# Microcontroller.net
KiCad netlist of a schematic drawn in Altium Designer
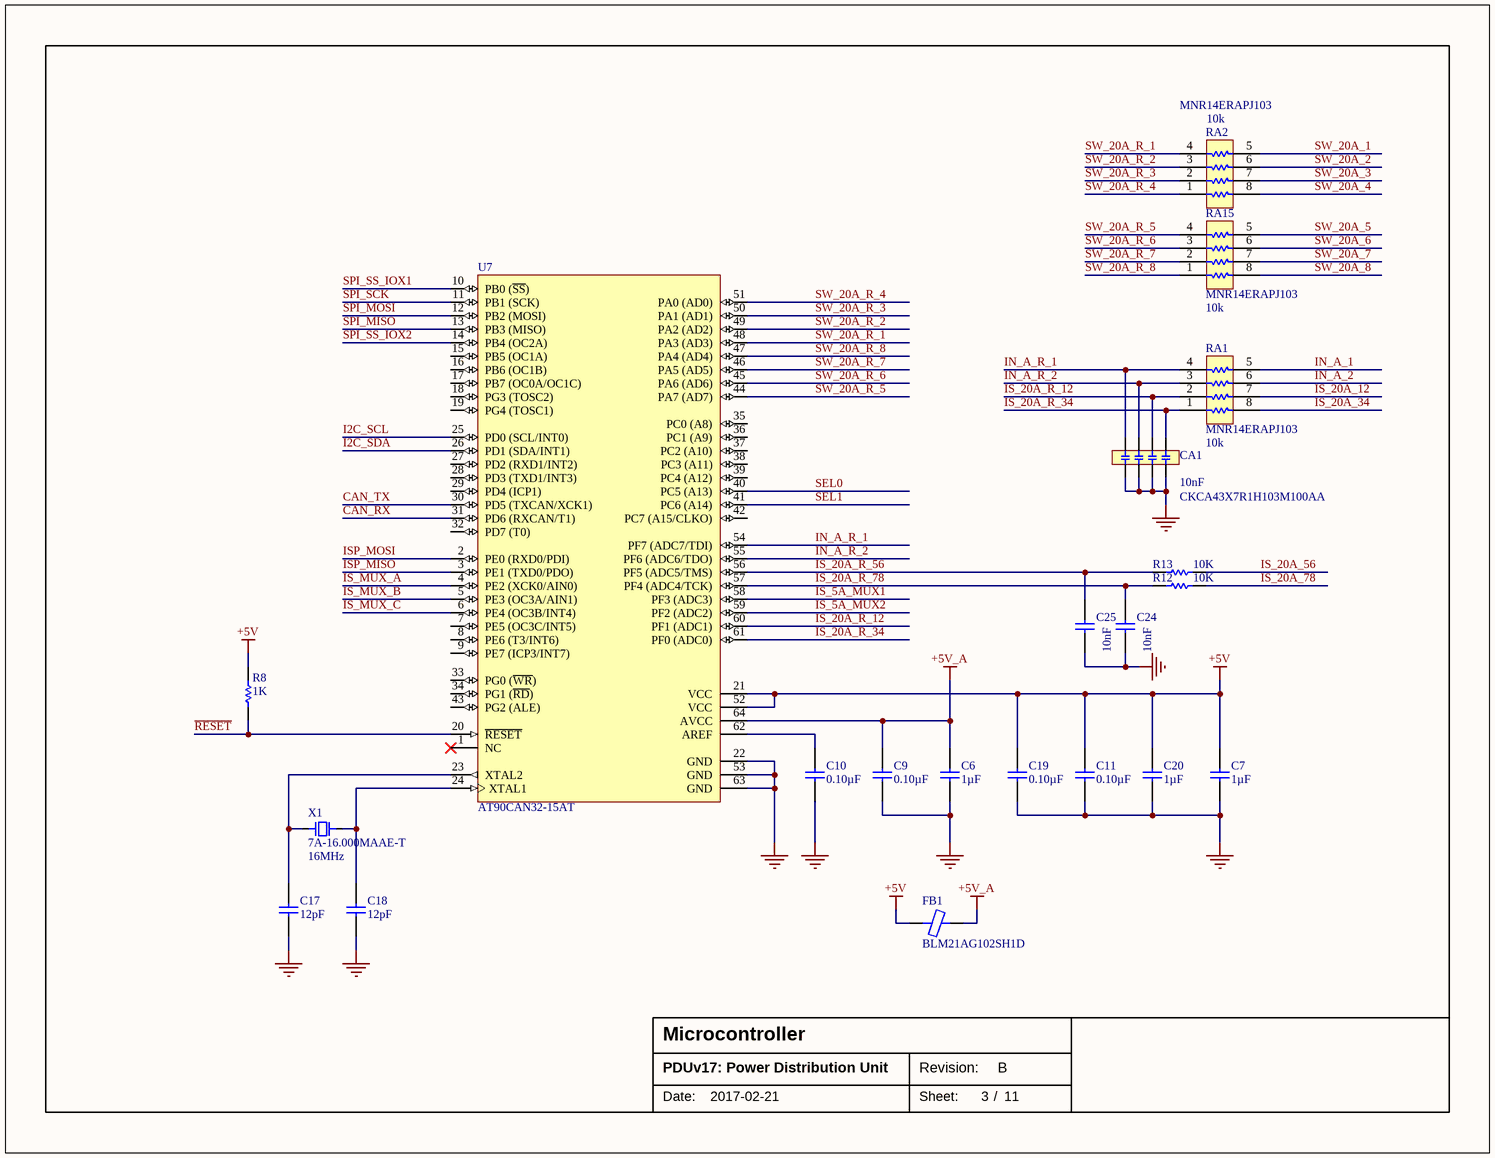
[diagram p0: Microcontroller.SchDoc]

(export (version "E")
  (design (tool "Eeschema 10.0.6"))
  (components
    (comp (ref "C6")
      (value "1µF")
      (footprint "CAP-0805-M")
      (fields
        (field (name "PART NUMBER") "CC0805KKX7R7BB105")
        (field (name "TOLERANCE") "±10%")
        (field (name "VOLTAGE") "16V")
      )
      (libsource (lib "Capacitors") (part "Capacitor"))
    )
    (comp (ref "C7")
      (value "1µF")
      (footprint "CAP-0805-M")
      (fields
        (field (name "PART NUMBER") "CC0805KKX7R7BB105")
        (field (name "TOLERANCE") "±10%")
        (field (name "VOLTAGE") "16V")
      )
      (libsource (lib "Capacitors") (part "Capacitor"))
    )
    (comp (ref "C9")
      (value "0.10µF")
      (footprint "CAP-0402-M")
      (fields
        (field (name "PART NUMBER") "CC0402KRX7R7BB104")
        (field (name "TOLERANCE") "±10%")
        (field (name "VOLTAGE") "16V")
      )
      (libsource (lib "Capacitors") (part "Capacitor"))
    )
    (comp (ref "C10")
      (value "0.10µF")
      (footprint "CAP-0402-M")
      (fields
        (field (name "PART NUMBER") "CC0402KRX7R7BB104")
        (field (name "TOLERANCE") "±10%")
        (field (name "VOLTAGE") "16V")
      )
      (libsource (lib "Capacitors") (part "Capacitor"))
    )
    (comp (ref "C11")
      (value "0.10µF")
      (footprint "CAP-0402-M")
      (fields
        (field (name "PART NUMBER") "CC0402KRX7R7BB104")
        (field (name "TOLERANCE") "±10%")
        (field (name "VOLTAGE") "16V")
      )
      (libsource (lib "Capacitors") (part "Capacitor"))
    )
    (comp (ref "C17")
      (value "12pF")
      (footprint "CAP-0402-M")
      (fields
        (field (name "PART NUMBER") "CC0402JRNPO9BN120")
        (field (name "TOLERANCE") "±5%")
        (field (name "VOLTAGE") "50V")
      )
      (libsource (lib "Capacitors") (part "Capacitor"))
    )
    (comp (ref "C18")
      (value "12pF")
      (footprint "CAP-0402-M")
      (fields
        (field (name "PART NUMBER") "CC0402JRNPO9BN120")
        (field (name "TOLERANCE") "±5%")
        (field (name "VOLTAGE") "50V")
      )
      (libsource (lib "Capacitors") (part "Capacitor"))
    )
    (comp (ref "C19")
      (value "0.10µF")
      (footprint "CAP-0402-M")
      (fields
        (field (name "PART NUMBER") "CC0402KRX7R7BB104")
        (field (name "TOLERANCE") "±10%")
        (field (name "VOLTAGE") "16V")
      )
      (libsource (lib "Capacitors") (part "Capacitor"))
    )
    (comp (ref "C20")
      (value "1µF")
      (footprint "CAP-0805-M")
      (fields
        (field (name "PART NUMBER") "CC0805KKX7R7BB105")
        (field (name "TOLERANCE") "±10%")
        (field (name "VOLTAGE") "16V")
      )
      (libsource (lib "Capacitors") (part "Capacitor"))
    )
    (comp (ref "C24")
      (value "10nF")
      (footprint "CAP-0402-M")
      (fields
        (field (name "PART NUMBER") "CC0402KRX7R7BB103")
        (field (name "TOLERANCE") "±10%")
        (field (name "VOLTAGE") "16V")
      )
      (libsource (lib "Capacitors") (part "Capacitor"))
    )
    (comp (ref "C25")
      (value "10nF")
      (footprint "CAP-0402-M")
      (fields
        (field (name "PART NUMBER") "CC0402KRX7R7BB103")
        (field (name "TOLERANCE") "±10%")
        (field (name "VOLTAGE") "16V")
      )
      (libsource (lib "Capacitors") (part "Capacitor"))
    )
    (comp (ref "CA1")
      (value "CKCA43X7R1H103M100AA")
      (footprint "CAF-80P319X159-8N")
      (fields (field (name "ALTIUM_VALUE") "10nF"))
      (libsource (lib "PDU-UV17") (part "CKCA43X7R1H103M100AA"))
    )
    (comp (ref "FB1")
      (value "BLM21AG102SH1D")
      (footprint "INDC2012X11N")
      (libsource (lib "PDU-UV17") (part "BLM21AG102SH1D"))
    )
    (comp (ref "R8")
      (value "1K")
      (footprint "RES-0603-M")
      (fields
        (field (name "PART NUMBER") "RC0603FR-071KL")
        (field (name "TOLERANCE") "1%")
        (field (name "POWER") "1/10 W")
      )
      (libsource (lib "Resistors") (part "Resistor"))
    )
    (comp (ref "R12")
      (value "10K")
      (footprint "RES-0603-M")
      (fields
        (field (name "PART NUMBER") "RC0603FR-0710KL")
        (field (name "TOLERANCE") "1%")
        (field (name "POWER") "1/10 W")
      )
      (libsource (lib "Resistors") (part "Resistor"))
    )
    (comp (ref "R13")
      (value "10K")
      (footprint "RES-0603-M")
      (fields
        (field (name "PART NUMBER") "RC0603FR-0710KL")
        (field (name "TOLERANCE") "1%")
        (field (name "POWER") "1/10 W")
      )
      (libsource (lib "Resistors") (part "Resistor"))
    )
    (comp (ref "RA1")
      (value "MNR14ERAPJ103")
      (footprint "CAC-80P319X150-8N")
      (fields (field (name "ALTIUM_VALUE") "10k"))
      (libsource (lib "PDU-UV17") (part "MNR14ERAPJ103"))
    )
    (comp (ref "RA2")
      (value "MNR14ERAPJ103")
      (footprint "CAC-80P319X150-8N")
      (fields (field (name "ALTIUM_VALUE") "10k"))
      (libsource (lib "PDU-UV17") (part "MNR14ERAPJ103"))
    )
    (comp (ref "RA15")
      (value "MNR14ERAPJ103")
      (footprint "CAC-80P319X150-8N")
      (fields (field (name "ALTIUM_VALUE") "10k"))
      (libsource (lib "PDU-UV17") (part "MNR14ERAPJ103"))
    )
    (comp (ref "U7")
      (value "AT90CAN32-15AT")
      (footprint "TQFP80P1600X1600X120-64N")
      (libsource (lib "PDU-UV17") (part "AT90CAN32-15AT"))
    )
    (comp (ref "X1")
      (value "7A-16.000MAAE-T")
      (footprint "QFN200P500X320X135-2N")
      (description "SMD Crystal Oscillator 12 pF")
      (fields (field (name "ALTIUM_VALUE") "16MHz"))
      (libsource (lib "PDUv2") (part "7A-16.000MAAE-T"))
    )
  )
  (nets
    (net (code "1") (name "+5V") (class "Default")
      (node (ref "C11") (pin "2") (pinfunction "2_2") (pintype "passive"))
      (node (ref "C19") (pin "2") (pinfunction "2_2") (pintype "passive"))
      (node (ref "C20") (pin "1") (pinfunction "1_1") (pintype "passive"))
      (node (ref "C7") (pin "1") (pinfunction "1_1") (pintype "passive"))
      (node (ref "FB1") (pin "1") (pinfunction "1_1") (pintype "passive"))
      (node (ref "R8") (pin "1") (pinfunction "1_1") (pintype "passive"))
      (node (ref "U7") (pin "21") (pinfunction "VCC_21") (pintype "power_in"))
      (node (ref "U7") (pin "52") (pinfunction "VCC_52") (pintype "power_in"))
    )
    (net (code "2") (name "+5V_A") (class "Default")
      (node (ref "C6") (pin "1") (pinfunction "1_1") (pintype "passive"))
      (node (ref "C9") (pin "2") (pinfunction "2_2") (pintype "passive"))
      (node (ref "FB1") (pin "2") (pinfunction "2_2") (pintype "passive"))
      (node (ref "U7") (pin "64") (pinfunction "AVCC_64") (pintype "power_in"))
    )
    (net (code "3") (name "/CAN_RX") (class "Default")
      (node (ref "U7") (pin "31") (pinfunction "PD6_(RXCAN/T1)_31") (pintype "bidirectional"))
    )
    (net (code "4") (name "/CAN_TX") (class "Default")
      (node (ref "U7") (pin "30") (pinfunction "PD5_(TXCAN/XCK1)_30") (pintype "bidirectional"))
    )
    (net (code "5") (name "/I2C_SCL") (class "Default")
      (node (ref "U7") (pin "25") (pinfunction "PD0_(SCL/INT0)_25") (pintype "bidirectional"))
    )
    (net (code "6") (name "/I2C_SDA") (class "Default")
      (node (ref "U7") (pin "26") (pinfunction "PD1_(SDA/INT1)_26") (pintype "bidirectional"))
    )
    (net (code "7") (name "/IN_A_1") (class "Default")
      (node (ref "RA1") (pin "5") (pinfunction "5_5") (pintype "passive"))
    )
    (net (code "8") (name "/IN_A_2") (class "Default")
      (node (ref "RA1") (pin "6") (pinfunction "6_6") (pintype "passive"))
    )
    (net (code "9") (name "/IN_A_R_1") (class "Default")
      (node (ref "CA1") (pin "5") (pinfunction "5_5") (pintype "passive"))
      (node (ref "RA1") (pin "4") (pinfunction "4_4") (pintype "passive"))
      (node (ref "U7") (pin "54") (pinfunction "PF7_(ADC7/TDI)_54") (pintype "bidirectional"))
    )
    (net (code "10") (name "/IN_A_R_2") (class "Default")
      (node (ref "CA1") (pin "6") (pinfunction "6_6") (pintype "passive"))
      (node (ref "RA1") (pin "3") (pinfunction "3_3") (pintype "passive"))
      (node (ref "U7") (pin "55") (pinfunction "PF6_(ADC6/TDO)_55") (pintype "bidirectional"))
    )
    (net (code "11") (name "/ISP_MISO") (class "Default")
      (node (ref "U7") (pin "3") (pinfunction "PE1_(TXD0/PDO)_3") (pintype "bidirectional"))
    )
    (net (code "12") (name "/ISP_MOSI") (class "Default")
      (node (ref "U7") (pin "2") (pinfunction "PE0_(RXD0/PDI)_2") (pintype "bidirectional"))
    )
    (net (code "13") (name "/IS_5A_MUX1") (class "Default")
      (node (ref "U7") (pin "58") (pinfunction "PF3_(ADC3)_58") (pintype "bidirectional"))
    )
    (net (code "14") (name "/IS_5A_MUX2") (class "Default")
      (node (ref "U7") (pin "59") (pinfunction "PF2_(ADC2)_59") (pintype "bidirectional"))
    )
    (net (code "15") (name "/IS_20A_12") (class "Default")
      (node (ref "RA1") (pin "7") (pinfunction "7_7") (pintype "passive"))
    )
    (net (code "16") (name "/IS_20A_34") (class "Default")
      (node (ref "RA1") (pin "8") (pinfunction "8_8") (pintype "passive"))
    )
    (net (code "17") (name "/IS_20A_56") (class "Default")
      (node (ref "R13") (pin "1") (pinfunction "1_1") (pintype "passive"))
    )
    (net (code "18") (name "/IS_20A_78") (class "Default")
      (node (ref "R12") (pin "1") (pinfunction "1_1") (pintype "passive"))
    )
    (net (code "19") (name "/IS_20A_R_12") (class "Default")
      (node (ref "CA1") (pin "7") (pinfunction "7_7") (pintype "passive"))
      (node (ref "RA1") (pin "2") (pinfunction "2_2") (pintype "passive"))
      (node (ref "U7") (pin "60") (pinfunction "PF1_(ADC1)_60") (pintype "bidirectional"))
    )
    (net (code "20") (name "/IS_20A_R_34") (class "Default")
      (node (ref "CA1") (pin "8") (pinfunction "8_8") (pintype "passive"))
      (node (ref "RA1") (pin "1") (pinfunction "1_1") (pintype "passive"))
      (node (ref "U7") (pin "61") (pinfunction "PF0_(ADC0)_61") (pintype "bidirectional"))
    )
    (net (code "21") (name "/IS_20A_R_56") (class "Default")
      (node (ref "C25") (pin "2") (pinfunction "2_2") (pintype "passive"))
      (node (ref "R13") (pin "2") (pinfunction "2_2") (pintype "passive"))
      (node (ref "U7") (pin "56") (pinfunction "PF5_(ADC5/TMS)_56") (pintype "bidirectional"))
    )
    (net (code "22") (name "/IS_20A_R_78") (class "Default")
      (node (ref "C24") (pin "2") (pinfunction "2_2") (pintype "passive"))
      (node (ref "R12") (pin "2") (pinfunction "2_2") (pintype "passive"))
      (node (ref "U7") (pin "57") (pinfunction "PF4_(ADC4/TCK)_57") (pintype "bidirectional"))
    )
    (net (code "23") (name "/IS_MUX_A") (class "Default")
      (node (ref "U7") (pin "4") (pinfunction "PE2_(XCK0/AIN0)_4") (pintype "bidirectional"))
    )
    (net (code "24") (name "/IS_MUX_B") (class "Default")
      (node (ref "U7") (pin "5") (pinfunction "PE3_(OC3A/AIN1)_5") (pintype "bidirectional"))
    )
    (net (code "25") (name "/IS_MUX_C") (class "Default")
      (node (ref "U7") (pin "6") (pinfunction "PE4_(OC3B/INT4)_6") (pintype "bidirectional"))
    )
    (net (code "26") (name "/SEL0") (class "Default")
      (node (ref "U7") (pin "40") (pinfunction "PC5_(A13)_40") (pintype "bidirectional"))
    )
    (net (code "27") (name "/SEL1") (class "Default")
      (node (ref "U7") (pin "41") (pinfunction "PC6_(A14)_41") (pintype "bidirectional"))
    )
    (net (code "28") (name "/SPI_MISO") (class "Default")
      (node (ref "U7") (pin "13") (pinfunction "PB3_(MISO)_13") (pintype "bidirectional"))
    )
    (net (code "29") (name "/SPI_MOSI") (class "Default")
      (node (ref "U7") (pin "12") (pinfunction "PB2_(MOSI)_12") (pintype "bidirectional"))
    )
    (net (code "30") (name "/SPI_SCK") (class "Default")
      (node (ref "U7") (pin "11") (pinfunction "PB1_(SCK)_11") (pintype "bidirectional"))
    )
    (net (code "31") (name "/SPI_SS_IOX1") (class "Default")
      (node (ref "U7") (pin "10") (pinfunction "PB0_(~{SS})_10") (pintype "bidirectional"))
    )
    (net (code "32") (name "/SPI_SS_IOX2") (class "Default")
      (node (ref "U7") (pin "14") (pinfunction "PB4_(OC2A)_14") (pintype "bidirectional"))
    )
    (net (code "33") (name "/SW_20A_1") (class "Default")
      (node (ref "RA2") (pin "5") (pinfunction "5_5") (pintype "passive"))
    )
    (net (code "34") (name "/SW_20A_2") (class "Default")
      (node (ref "RA2") (pin "6") (pinfunction "6_6") (pintype "passive"))
    )
    (net (code "35") (name "/SW_20A_3") (class "Default")
      (node (ref "RA2") (pin "7") (pinfunction "7_7") (pintype "passive"))
    )
    (net (code "36") (name "/SW_20A_4") (class "Default")
      (node (ref "RA2") (pin "8") (pinfunction "8_8") (pintype "passive"))
    )
    (net (code "37") (name "/SW_20A_5") (class "Default")
      (node (ref "RA15") (pin "5") (pinfunction "5_5") (pintype "passive"))
    )
    (net (code "38") (name "/SW_20A_6") (class "Default")
      (node (ref "RA15") (pin "6") (pinfunction "6_6") (pintype "passive"))
    )
    (net (code "39") (name "/SW_20A_7") (class "Default")
      (node (ref "RA15") (pin "7") (pinfunction "7_7") (pintype "passive"))
    )
    (net (code "40") (name "/SW_20A_8") (class "Default")
      (node (ref "RA15") (pin "8") (pinfunction "8_8") (pintype "passive"))
    )
    (net (code "41") (name "/SW_20A_R_1") (class "Default")
      (node (ref "RA2") (pin "4") (pinfunction "4_4") (pintype "passive"))
      (node (ref "U7") (pin "48") (pinfunction "PA3_(AD3)_48") (pintype "bidirectional"))
    )
    (net (code "42") (name "/SW_20A_R_2") (class "Default")
      (node (ref "RA2") (pin "3") (pinfunction "3_3") (pintype "passive"))
      (node (ref "U7") (pin "49") (pinfunction "PA2_(AD2)_49") (pintype "bidirectional"))
    )
    (net (code "43") (name "/SW_20A_R_3") (class "Default")
      (node (ref "RA2") (pin "2") (pinfunction "2_2") (pintype "passive"))
      (node (ref "U7") (pin "50") (pinfunction "PA1_(AD1)_50") (pintype "bidirectional"))
    )
    (net (code "44") (name "/SW_20A_R_4") (class "Default")
      (node (ref "RA2") (pin "1") (pinfunction "1_1") (pintype "passive"))
      (node (ref "U7") (pin "51") (pinfunction "PA0_(AD0)_51") (pintype "bidirectional"))
    )
    (net (code "45") (name "/SW_20A_R_5") (class "Default")
      (node (ref "RA15") (pin "4") (pinfunction "4_4") (pintype "passive"))
      (node (ref "U7") (pin "44") (pinfunction "PA7_(AD7)_44") (pintype "bidirectional"))
    )
    (net (code "46") (name "/SW_20A_R_6") (class "Default")
      (node (ref "RA15") (pin "3") (pinfunction "3_3") (pintype "passive"))
      (node (ref "U7") (pin "45") (pinfunction "PA6_(AD6)_45") (pintype "bidirectional"))
    )
    (net (code "47") (name "/SW_20A_R_7") (class "Default")
      (node (ref "RA15") (pin "2") (pinfunction "2_2") (pintype "passive"))
      (node (ref "U7") (pin "46") (pinfunction "PA5_(AD5)_46") (pintype "bidirectional"))
    )
    (net (code "48") (name "/SW_20A_R_8") (class "Default")
      (node (ref "RA15") (pin "1") (pinfunction "1_1") (pintype "passive"))
      (node (ref "U7") (pin "47") (pinfunction "PA4_(AD4)_47") (pintype "bidirectional"))
    )
    (net (code "49") (name "/~{RESET}") (class "Default")
      (node (ref "R8") (pin "2") (pinfunction "2_2") (pintype "passive"))
      (node (ref "U7") (pin "20") (pinfunction "~{RESET}_20") (pintype "input"))
    )
    (net (code "50") (name "GND") (class "Default")
      (node (ref "C10") (pin "1") (pinfunction "1_1") (pintype "passive"))
      (node (ref "C11") (pin "1") (pinfunction "1_1") (pintype "passive"))
      (node (ref "C17") (pin "1") (pinfunction "1_1") (pintype "passive"))
      (node (ref "C18") (pin "1") (pinfunction "1_1") (pintype "passive"))
      (node (ref "C19") (pin "1") (pinfunction "1_1") (pintype "passive"))
      (node (ref "C20") (pin "2") (pinfunction "2_2") (pintype "passive"))
      (node (ref "C24") (pin "1") (pinfunction "1_1") (pintype "passive"))
      (node (ref "C25") (pin "1") (pinfunction "1_1") (pintype "passive"))
      (node (ref "C6") (pin "2") (pinfunction "2_2") (pintype "passive"))
      (node (ref "C7") (pin "2") (pinfunction "2_2") (pintype "passive"))
      (node (ref "C9") (pin "1") (pinfunction "1_1") (pintype "passive"))
      (node (ref "CA1") (pin "1") (pinfunction "1_1") (pintype "passive"))
      (node (ref "CA1") (pin "2") (pinfunction "2_2") (pintype "passive"))
      (node (ref "CA1") (pin "3") (pinfunction "3_3") (pintype "passive"))
      (node (ref "CA1") (pin "4") (pinfunction "4_4") (pintype "passive"))
      (node (ref "U7") (pin "22") (pinfunction "GND_22") (pintype "power_in"))
      (node (ref "U7") (pin "53") (pinfunction "GND_53") (pintype "power_in"))
      (node (ref "U7") (pin "63") (pinfunction "GND_63") (pintype "power_in"))
    )
    (net (code "51") (name "Net-(U7-AREF)") (class "Default")
      (node (ref "C10") (pin "2") (pinfunction "2_2") (pintype "passive"))
      (node (ref "U7") (pin "62") (pinfunction "AREF_62") (pintype "power_in"))
    )
    (net (code "52") (name "Net-(U7-XTAL1)") (class "Default")
      (node (ref "C18") (pin "2") (pinfunction "2_2") (pintype "passive"))
      (node (ref "U7") (pin "24") (pinfunction "XTAL1_24") (pintype "input"))
      (node (ref "X1") (pin "2") (pinfunction "2_2") (pintype "passive"))
    )
    (net (code "53") (name "Net-(U7-XTAL2)") (class "Default")
      (node (ref "C17") (pin "2") (pinfunction "2_2") (pintype "passive"))
      (node (ref "U7") (pin "23") (pinfunction "XTAL2_23") (pintype "output"))
      (node (ref "X1") (pin "1") (pinfunction "1_1") (pintype "passive"))
    )
    (net (code "54") (name "unconnected-(U7-NC-Pad1)") (class "Default")
      (node (ref "U7") (pin "1") (pinfunction "NC_1") (pintype "passive+no_connect"))
    )
    (net (code "55") (name "unconnected-(U7-PB5_(OC1A)-Pad15)") (class "Default")
      (node (ref "U7") (pin "15") (pinfunction "PB5_(OC1A)_15") (pintype "bidirectional"))
    )
    (net (code "56") (name "unconnected-(U7-PB6_(OC1B)-Pad16)") (class "Default")
      (node (ref "U7") (pin "16") (pinfunction "PB6_(OC1B)_16") (pintype "bidirectional"))
    )
    (net (code "57") (name "unconnected-(U7-PB7_(OC0A{slash}OC1C)-Pad17)") (class "Default")
      (node (ref "U7") (pin "17") (pinfunction "PB7_(OC0A/OC1C)_17") (pintype "bidirectional"))
    )
    (net (code "58") (name "unconnected-(U7-PC0_(A8)-Pad35)") (class "Default")
      (node (ref "U7") (pin "35") (pinfunction "PC0_(A8)_35") (pintype "bidirectional"))
    )
    (net (code "59") (name "unconnected-(U7-PC1_(A9)-Pad36)") (class "Default")
      (node (ref "U7") (pin "36") (pinfunction "PC1_(A9)_36") (pintype "bidirectional"))
    )
    (net (code "60") (name "unconnected-(U7-PC2_(A10)-Pad37)") (class "Default")
      (node (ref "U7") (pin "37") (pinfunction "PC2_(A10)_37") (pintype "bidirectional"))
    )
    (net (code "61") (name "unconnected-(U7-PC3_(A11)-Pad38)") (class "Default")
      (node (ref "U7") (pin "38") (pinfunction "PC3_(A11)_38") (pintype "bidirectional"))
    )
    (net (code "62") (name "unconnected-(U7-PC4_(A12)-Pad39)") (class "Default")
      (node (ref "U7") (pin "39") (pinfunction "PC4_(A12)_39") (pintype "bidirectional"))
    )
    (net (code "63") (name "unconnected-(U7-PC7_(A15{slash}CLKO)-Pad42)") (class "Default")
      (node (ref "U7") (pin "42") (pinfunction "PC7_(A15/CLKO)_42") (pintype "bidirectional"))
    )
    (net (code "64") (name "unconnected-(U7-PD2_(RXD1{slash}INT2)-Pad27)") (class "Default")
      (node (ref "U7") (pin "27") (pinfunction "PD2_(RXD1/INT2)_27") (pintype "bidirectional"))
    )
    (net (code "65") (name "unconnected-(U7-PD3_(TXD1{slash}INT3)-Pad28)") (class "Default")
      (node (ref "U7") (pin "28") (pinfunction "PD3_(TXD1/INT3)_28") (pintype "bidirectional"))
    )
    (net (code "66") (name "unconnected-(U7-PD4_(ICP1)-Pad29)") (class "Default")
      (node (ref "U7") (pin "29") (pinfunction "PD4_(ICP1)_29") (pintype "bidirectional"))
    )
    (net (code "67") (name "unconnected-(U7-PD7_(T0)-Pad32)") (class "Default")
      (node (ref "U7") (pin "32") (pinfunction "PD7_(T0)_32") (pintype "bidirectional"))
    )
    (net (code "68") (name "unconnected-(U7-PE5_(OC3C{slash}INT5)-Pad7)") (class "Default")
      (node (ref "U7") (pin "7") (pinfunction "PE5_(OC3C/INT5)_7") (pintype "bidirectional"))
    )
    (net (code "69") (name "unconnected-(U7-PE6_(T3{slash}INT6)-Pad8)") (class "Default")
      (node (ref "U7") (pin "8") (pinfunction "PE6_(T3/INT6)_8") (pintype "bidirectional"))
    )
    (net (code "70") (name "unconnected-(U7-PE7_(ICP3{slash}INT7)-Pad9)") (class "Default")
      (node (ref "U7") (pin "9") (pinfunction "PE7_(ICP3/INT7)_9") (pintype "bidirectional"))
    )
    (net (code "71") (name "unconnected-(U7-PG0_(~{WR})-Pad33)") (class "Default")
      (node (ref "U7") (pin "33") (pinfunction "PG0_(~{WR})_33") (pintype "bidirectional"))
    )
    (net (code "72") (name "unconnected-(U7-PG1_(~{RD})-Pad34)") (class "Default")
      (node (ref "U7") (pin "34") (pinfunction "PG1_(~{RD})_34") (pintype "bidirectional"))
    )
    (net (code "73") (name "unconnected-(U7-PG2_(ALE)-Pad43)") (class "Default")
      (node (ref "U7") (pin "43") (pinfunction "PG2_(ALE)_43") (pintype "bidirectional"))
    )
    (net (code "74") (name "unconnected-(U7-PG3_(TOSC2)-Pad18)") (class "Default")
      (node (ref "U7") (pin "18") (pinfunction "PG3_(TOSC2)_18") (pintype "bidirectional"))
    )
    (net (code "75") (name "unconnected-(U7-PG4_(TOSC1)-Pad19)") (class "Default")
      (node (ref "U7") (pin "19") (pinfunction "PG4_(TOSC1)_19") (pintype "bidirectional"))
    )
  )
)
